# schematic.net
KiCad netlist of a schematic drawn in EAGLE
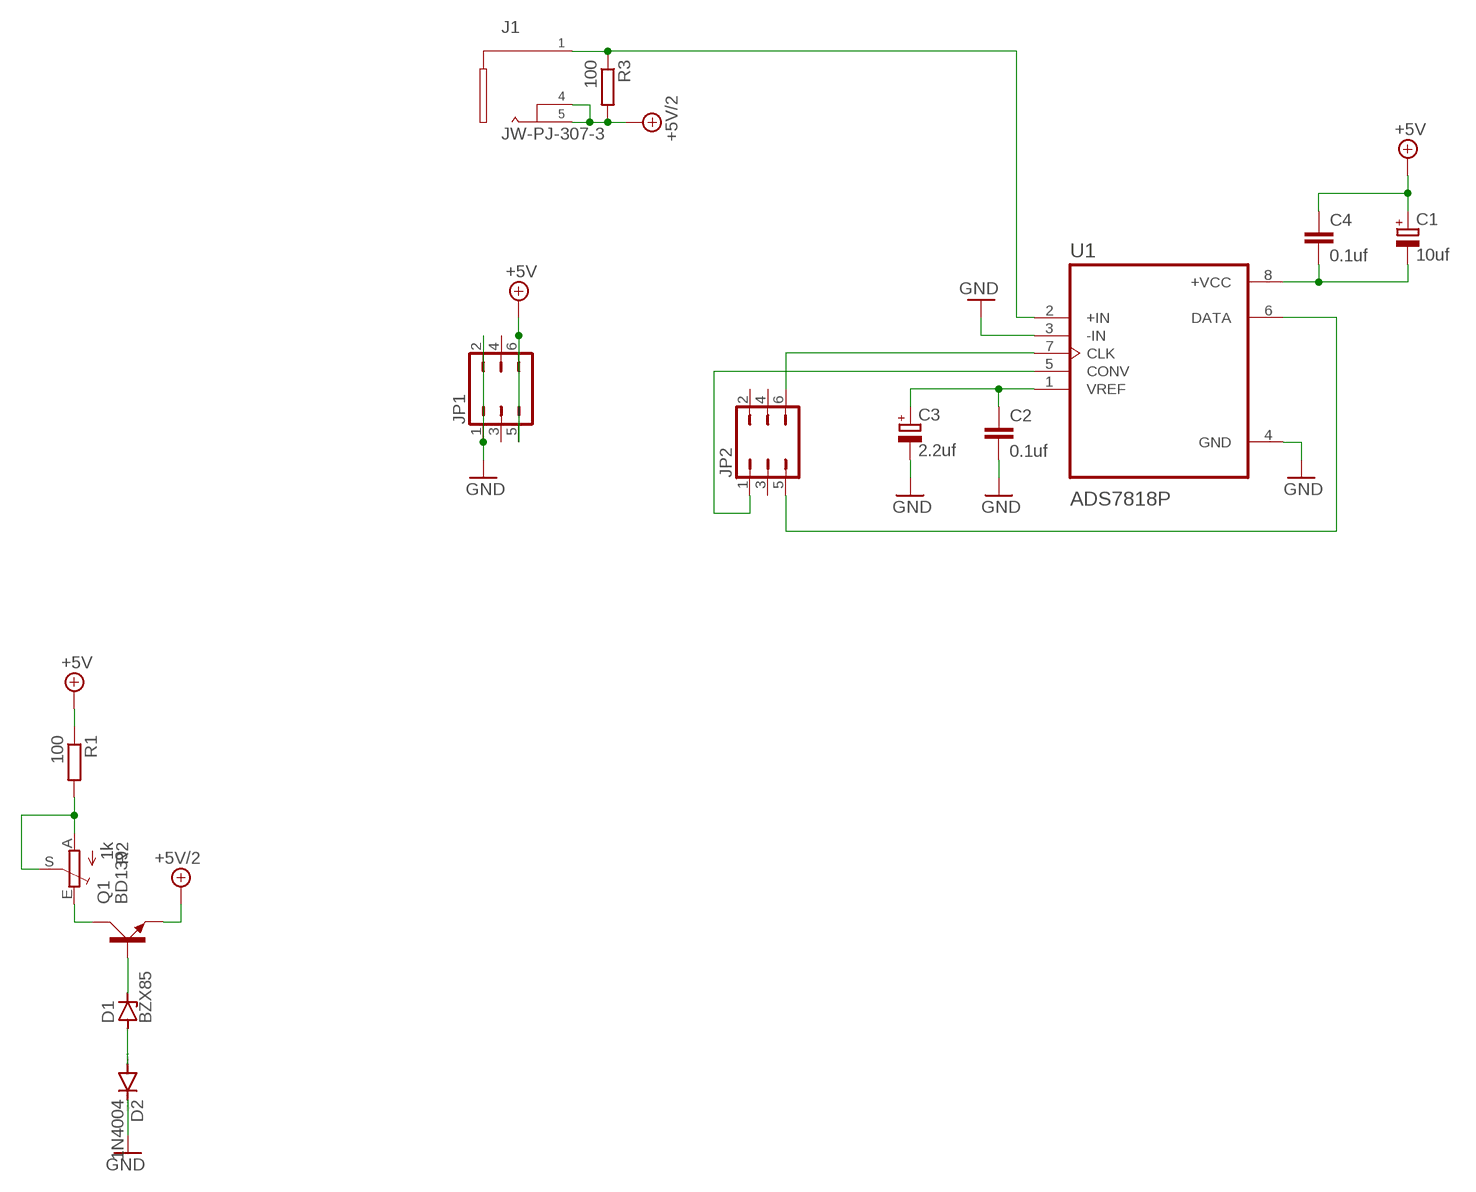
[diagram p0: schematic, sheet 1]

(export (version "E")
  (design (tool "Eeschema 10.0.6"))
  (components
    (comp (ref "C1")
      (value "10uf")
      (footprint "eagle-import:E3,5-8")
      (libsource (lib "eagle-import") (part "CPOL-EUE3.5-8"))
    )
    (comp (ref "C2")
      (value "0.1uf")
      (footprint "eagle-import:C050-030X075")
      (libsource (lib "eagle-import") (part "C-EU050-030X075"))
    )
    (comp (ref "C3")
      (value "2.2uf")
      (footprint "eagle-import:E2,5-6")
      (libsource (lib "eagle-import") (part "CPOL-EUE2.5-6"))
    )
    (comp (ref "C4")
      (value "0.1uf")
      (footprint "eagle-import:C050-030X075")
      (libsource (lib "eagle-import") (part "C-EU050-030X075"))
    )
    (comp (ref "D1")
      (value "BZX85")
      (footprint "eagle-import:DO41Z10")
      (libsource (lib "eagle-import") (part "BZX85"))
    )
    (comp (ref "D2")
      (value "1N4004")
      (footprint "eagle-import:DO41-10")
      (libsource (lib "eagle-import") (part "1N4004"))
    )
    (comp (ref "J1")
      (value "JW-PJ-307-3")
      (footprint "eagle-import:JW-PJ-307-X")
      (libsource (lib "eagle-import") (part "JW-PJ-307-3"))
    )
    (comp (ref "JP1")
      (value "JP3Q")
      (footprint "eagle-import:JP3Q")
      (libsource (lib "eagle-import") (part "JP3Q"))
    )
    (comp (ref "JP2")
      (value "JP3Q")
      (footprint "eagle-import:JP3Q")
      (libsource (lib "eagle-import") (part "JP3Q"))
    )
    (comp (ref "Q1")
      (value "BD139")
      (footprint "eagle-import:TO126AV")
      (libsource (lib "eagle-import") (part "BD139"))
    )
    (comp (ref "R1")
      (value "100")
      (footprint "eagle-import:0207_10")
      (libsource (lib "eagle-import") (part "R-EU_0207/10"))
    )
    (comp (ref "R2")
      (value "1k")
      (footprint "eagle-import:CA9V")
      (libsource (lib "eagle-import") (part "TRIM_EU-CA9V"))
    )
    (comp (ref "R3")
      (value "100")
      (footprint "eagle-import:0207_10")
      (libsource (lib "eagle-import") (part "R-EU_0207/10"))
    )
    (comp (ref "U1")
      (value "ADS7818P")
      (footprint "eagle-import:DIP794W45P254L959H508Q8")
      (fields (field (name "MF") "Texas Instruments"))
      (libsource (lib "eagle-import") (part "ADS7818P"))
    )
  )
  (nets
    (net (code "1") (name "+5V") (class "Default")
      (node (ref "C1") (pin "+") (pinfunction "+_+") (pintype "passive"))
      (node (ref "C4") (pin "1") (pinfunction "1_1") (pintype "passive"))
      (node (ref "JP1") (pin "5") (pinfunction "5_5") (pintype "passive"))
      (node (ref "JP1") (pin "6") (pinfunction "6_6") (pintype "passive"))
      (node (ref "R1") (pin "1") (pinfunction "1_1") (pintype "passive"))
    )
    (net (code "2") (name "+5V{slash}2") (class "Default")
      (node (ref "J1") (pin "P$4") (pinfunction "4_P$4") (pintype "passive"))
      (node (ref "J1") (pin "P$5") (pinfunction "5_P$5") (pintype "passive"))
      (node (ref "Q1") (pin "E") (pinfunction "E_E") (pintype "passive"))
      (node (ref "R3") (pin "2") (pinfunction "2_2") (pintype "passive"))
    )
    (net (code "3") (name "GND") (class "Default")
      (node (ref "C2") (pin "2") (pinfunction "2_2") (pintype "passive"))
      (node (ref "C3") (pin "-") (pinfunction "-_-") (pintype "passive"))
      (node (ref "D2") (pin "C") (pinfunction "C_C") (pintype "passive"))
      (node (ref "JP1") (pin "1") (pinfunction "1_1") (pintype "passive"))
      (node (ref "JP1") (pin "2") (pinfunction "2_2") (pintype "passive"))
      (node (ref "U1") (pin "3") (pinfunction "-IN_3") (pintype "input"))
      (node (ref "U1") (pin "4") (pinfunction "GND_4") (pintype "power_in"))
    )
    (net (code "4") (name "Net-(D1-PadA)") (class "Default")
      (node (ref "D1") (pin "A") (pinfunction "A_A") (pintype "passive"))
      (node (ref "D2") (pin "A") (pinfunction "A_A") (pintype "passive"))
    )
    (net (code "5") (name "Net-(D1-PadC)") (class "Default")
      (node (ref "D1") (pin "C") (pinfunction "C_C") (pintype "passive"))
      (node (ref "Q1") (pin "B") (pinfunction "B_B") (pintype "passive"))
    )
    (net (code "6") (name "Net-(J1-1)") (class "Default")
      (node (ref "J1") (pin "P$1") (pinfunction "1_P$1") (pintype "passive"))
      (node (ref "R3") (pin "1") (pinfunction "1_1") (pintype "passive"))
      (node (ref "U1") (pin "2") (pinfunction "+IN_2") (pintype "input"))
    )
    (net (code "7") (name "Net-(Q1-PadC)") (class "Default")
      (node (ref "Q1") (pin "C") (pinfunction "C_C") (pintype "passive"))
      (node (ref "R2") (pin "E") (pinfunction "E_E") (pintype "passive"))
    )
    (net (code "8") (name "Net-(R1-Pad2)") (class "Default")
      (node (ref "R1") (pin "2") (pinfunction "2_2") (pintype "passive"))
      (node (ref "R2") (pin "A") (pinfunction "A_A") (pintype "passive"))
      (node (ref "R2") (pin "S") (pinfunction "S_S") (pintype "passive"))
    )
    (net (code "9") (name "Net-(U1-+VCC)") (class "Default")
      (node (ref "C1") (pin "-") (pinfunction "-_-") (pintype "passive"))
      (node (ref "C4") (pin "2") (pinfunction "2_2") (pintype "passive"))
      (node (ref "U1") (pin "8") (pinfunction "+VCC_8") (pintype "power_in"))
    )
    (net (code "10") (name "Net-(U1-CLK)") (class "Default")
      (node (ref "JP2") (pin "6") (pinfunction "6_6") (pintype "passive"))
      (node (ref "U1") (pin "7") (pinfunction "CLK_7") (pintype "input"))
    )
    (net (code "11") (name "Net-(U1-CONV)") (class "Default")
      (node (ref "JP2") (pin "1") (pinfunction "1_1") (pintype "passive"))
      (node (ref "U1") (pin "5") (pinfunction "CONV_5") (pintype "input"))
    )
    (net (code "12") (name "Net-(U1-DATA)") (class "Default")
      (node (ref "JP2") (pin "5") (pinfunction "5_5") (pintype "passive"))
      (node (ref "U1") (pin "6") (pinfunction "DATA_6") (pintype "output"))
    )
    (net (code "13") (name "Net-(U1-VREF)") (class "Default")
      (node (ref "C2") (pin "1") (pinfunction "1_1") (pintype "passive"))
      (node (ref "C3") (pin "+") (pinfunction "+_+") (pintype "passive"))
      (node (ref "U1") (pin "1") (pinfunction "VREF_1") (pintype "input"))
    )
    (net (code "14") (name "unconnected-(JP1-Pad3)") (class "Default")
      (node (ref "JP1") (pin "3") (pinfunction "3_3") (pintype "passive"))
    )
    (net (code "15") (name "unconnected-(JP1-Pad4)") (class "Default")
      (node (ref "JP1") (pin "4") (pinfunction "4_4") (pintype "passive"))
    )
    (net (code "16") (name "unconnected-(JP2-Pad2)") (class "Default")
      (node (ref "JP2") (pin "2") (pinfunction "2_2") (pintype "passive"))
    )
    (net (code "17") (name "unconnected-(JP2-Pad3)") (class "Default")
      (node (ref "JP2") (pin "3") (pinfunction "3_3") (pintype "passive"))
    )
    (net (code "18") (name "unconnected-(JP2-Pad4)") (class "Default")
      (node (ref "JP2") (pin "4") (pinfunction "4_4") (pintype "passive"))
    )
  )
)
